# zigduino-v6b.net
KiCad netlist of a schematic drawn in EAGLE
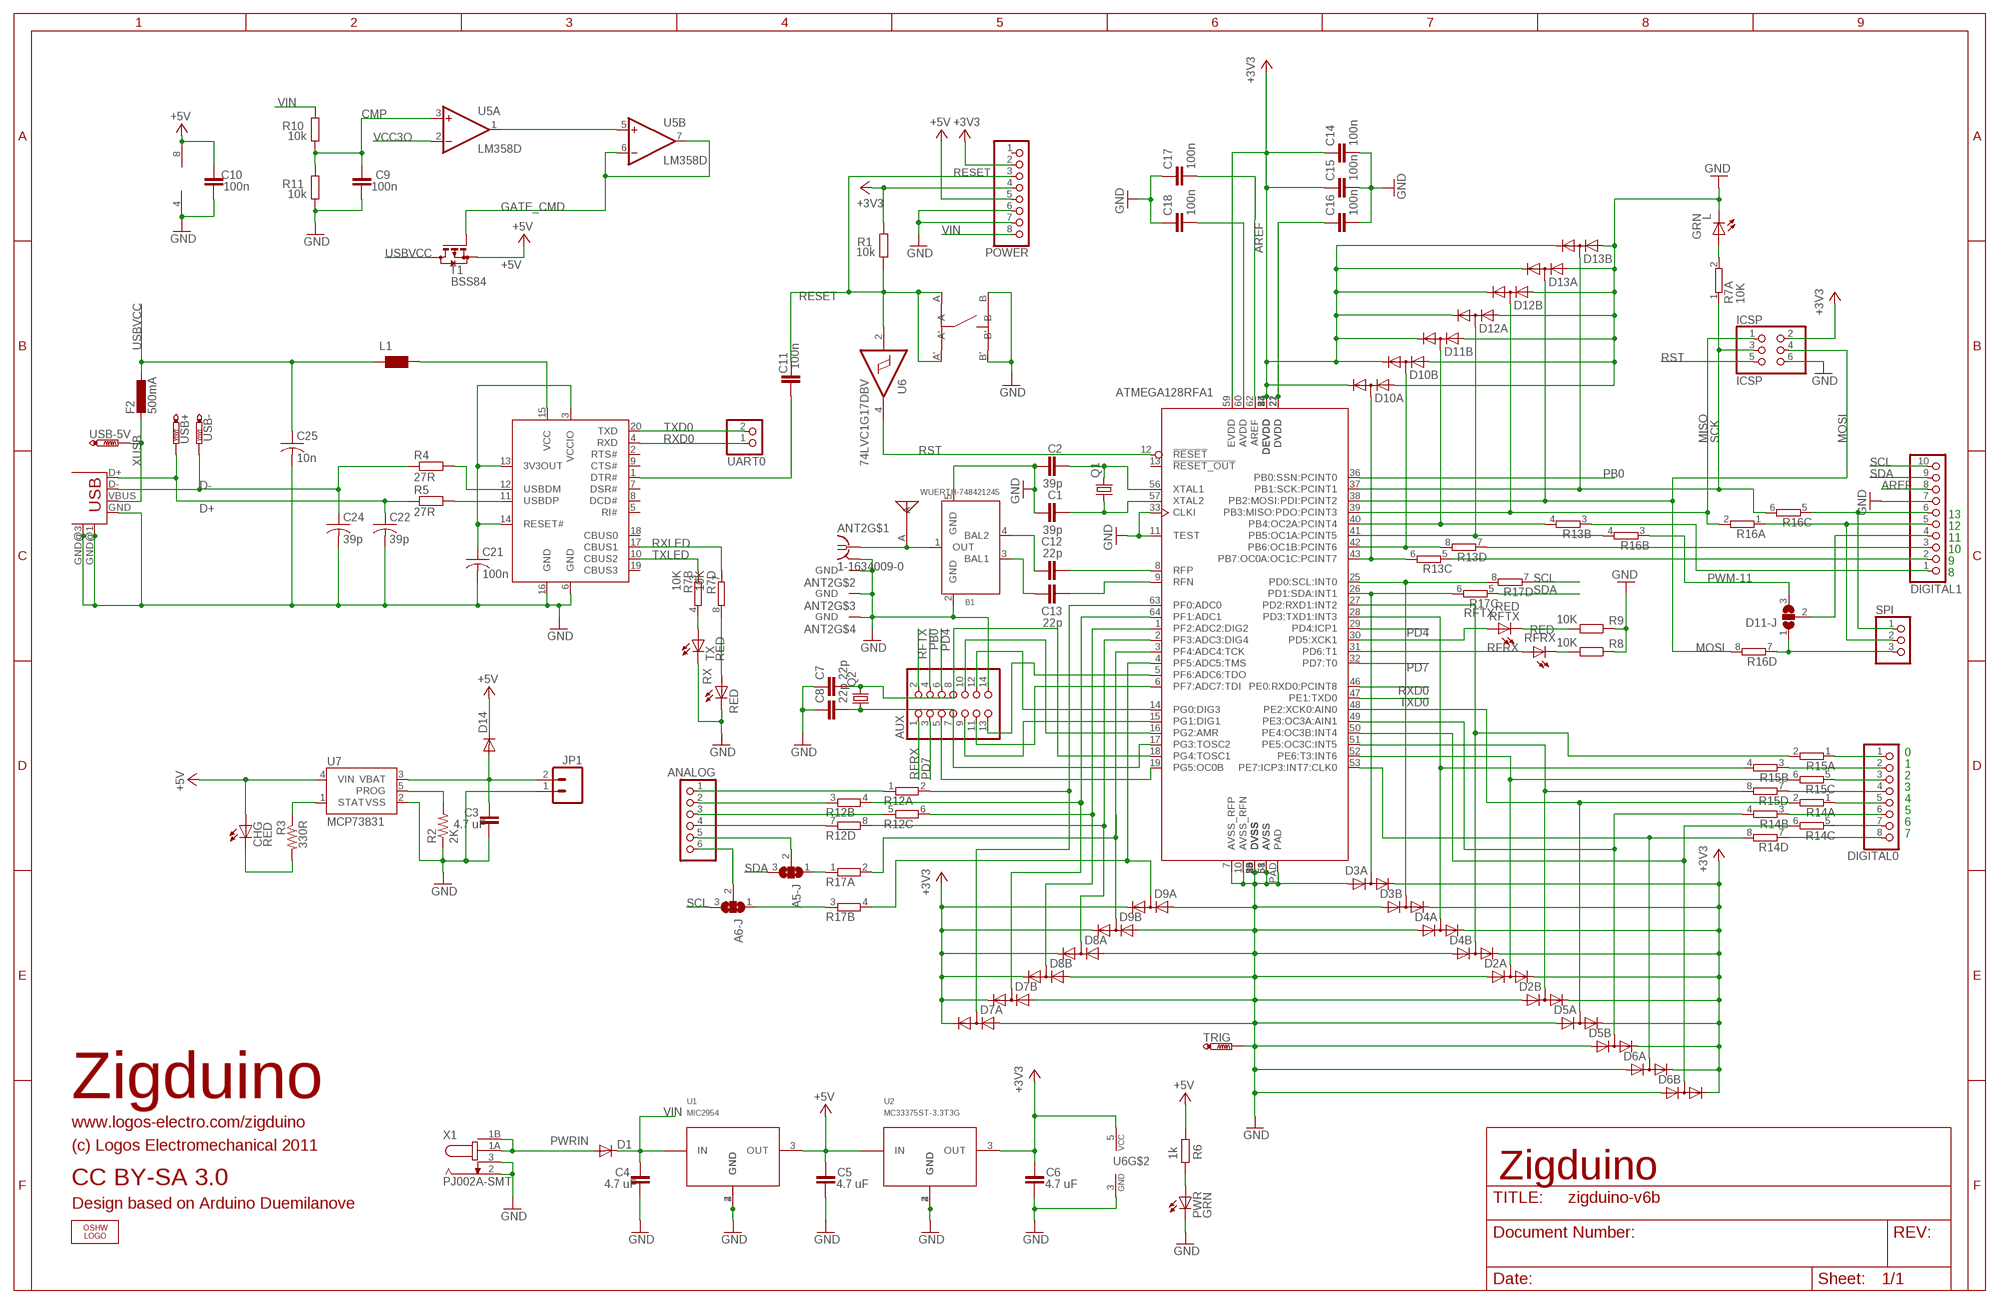
[diagram p0: schematic, sheet 1]

(export (version "E")
  (design (tool "Eeschema 10.0.6"))
  (components
    (comp (ref "A5-J")
      (value "SJ2W")
      (footprint "eagle-import:SJ_2")
      (fields (field (name "PARTNO") "SJ3"))
      (libsource (lib "eagle-import") (part "SJ2W"))
    )
    (comp (ref "A6-J")
      (value "SJ2W")
      (footprint "eagle-import:SJ_2")
      (fields (field (name "PARTNO") "SJ3"))
      (libsource (lib "eagle-import") (part "SJ2W"))
    )
    (comp (ref "ANALOG")
      (value "PINHD-1X6")
      (footprint "eagle-import:1X06")
      (fields (field (name "PARTNO") "19742"))
      (libsource (lib "eagle-import") (part "PINHD-1X6"))
    )
    (comp (ref "ANT1")
      (value "MOLEX-ANT")
      (footprint "eagle-import:MOLEX-ANT")
      (fields (field (name "PARTNO") "0479480001"))
      (libsource (lib "eagle-import") (part "MOLEX-ANT"))
    )
    (comp (ref "ANT2")
      (value "1-1634009-0")
      (footprint "eagle-import:MMCX-THRU")
      (fields (field (name "BOM") "EXCLUDE") (field (name "DNP") "T"))
      (libsource (lib "eagle-import") (part "1-1634009-0"))
    )
    (comp (ref "AUX")
      (value "PINHD-2X7_2.00")
      (footprint "eagle-import:2X07M")
      (fields (field (name "PARTNO") "00217"))
      (libsource (lib "eagle-import") (part "PINHD-2X7_2.00"))
    )
    (comp (ref "B1")
      (value "WUERTH-748421245")
      (footprint "eagle-import:WURTH-BALUN")
      (fields (field (name "PARTNO") "748421245"))
      (libsource (lib "eagle-import") (part "WUERTH-748421245"))
    )
    (comp (ref "C1")
      (value "39p")
      (footprint "eagle-import:C0603")
      (fields (field (name "PARTNO") "C1608C0G1H390J"))
      (libsource (lib "eagle-import") (part "C-EUC0603"))
    )
    (comp (ref "C2")
      (value "39p")
      (footprint "eagle-import:C0603")
      (fields (field (name "PARTNO") "C1608C0G1H390J"))
      (libsource (lib "eagle-import") (part "C-EUC0603"))
    )
    (comp (ref "C3")
      (value "4.7 uF")
      (footprint "eagle-import:C1206")
      (fields (field (name "PARTNO") "C3216Y5V1H475Z"))
      (libsource (lib "eagle-import") (part "C-EUC1206"))
    )
    (comp (ref "C4")
      (value "4.7 uF")
      (footprint "eagle-import:C1206")
      (fields (field (name "PARTNO") "C3216Y5V1H475Z"))
      (libsource (lib "eagle-import") (part "C-EUC1206"))
    )
    (comp (ref "C5")
      (value "4.7 uF")
      (footprint "eagle-import:C1206")
      (fields (field (name "PARTNO") "C3216Y5V1H475Z"))
      (libsource (lib "eagle-import") (part "C-EUC1206"))
    )
    (comp (ref "C6")
      (value "4.7 uF")
      (footprint "eagle-import:C1206")
      (fields (field (name "PARTNO") "C3216Y5V1H475Z"))
      (libsource (lib "eagle-import") (part "C-EUC1206"))
    )
    (comp (ref "C7")
      (value "22p")
      (footprint "eagle-import:C0603")
      (fields (field (name "PARTNO") "GQM1885C1H220JB01D"))
      (libsource (lib "eagle-import") (part "C-EUC0603"))
    )
    (comp (ref "C8")
      (value "22p")
      (footprint "eagle-import:C0603")
      (fields (field (name "PARTNO") "GQM1885C1H220JB01D"))
      (libsource (lib "eagle-import") (part "C-EUC0603"))
    )
    (comp (ref "C9")
      (value "100n")
      (footprint "eagle-import:C0603")
      (fields (field (name "PARTNO") "CC0603MRY5V9BB104"))
      (libsource (lib "eagle-import") (part "C-EUC0603"))
    )
    (comp (ref "C10")
      (value "100n")
      (footprint "eagle-import:C0603")
      (fields (field (name "PARTNO") "CC0603MRY5V9BB104"))
      (libsource (lib "eagle-import") (part "C-EUC0603"))
    )
    (comp (ref "C11")
      (value "100n")
      (footprint "eagle-import:C0603")
      (fields (field (name "PARTNO") "CC0603MRY5V9BB104"))
      (libsource (lib "eagle-import") (part "C-EUC0603"))
    )
    (comp (ref "C12")
      (value "22p")
      (footprint "eagle-import:C0603")
      (fields (field (name "PARTNO") "GQM1885C1H220JB01D"))
      (libsource (lib "eagle-import") (part "C-EUC0603"))
    )
    (comp (ref "C13")
      (value "22p")
      (footprint "eagle-import:C0603")
      (fields (field (name "PARTNO") "GQM1885C1H220JB01D"))
      (libsource (lib "eagle-import") (part "C-EUC0603"))
    )
    (comp (ref "C14")
      (value "100n")
      (footprint "eagle-import:C0603")
      (fields (field (name "PARTNO") "CC0603MRY5V9BB104"))
      (libsource (lib "eagle-import") (part "C-EUC0603"))
    )
    (comp (ref "C15")
      (value "100n")
      (footprint "eagle-import:C0603")
      (fields (field (name "PARTNO") "CC0603MRY5V9BB104"))
      (libsource (lib "eagle-import") (part "C-EUC0603"))
    )
    (comp (ref "C16")
      (value "100n")
      (footprint "eagle-import:C0603")
      (fields (field (name "PARTNO") "CC0603MRY5V9BB104"))
      (libsource (lib "eagle-import") (part "C-EUC0603"))
    )
    (comp (ref "C17")
      (value "100n")
      (footprint "eagle-import:C0603")
      (fields (field (name "PARTNO") "CC0603MRY5V9BB104"))
      (libsource (lib "eagle-import") (part "C-EUC0603"))
    )
    (comp (ref "C18")
      (value "100n")
      (footprint "eagle-import:C0603")
      (fields (field (name "PARTNO") "CC0603MRY5V9BB104"))
      (libsource (lib "eagle-import") (part "C-EUC0603"))
    )
    (comp (ref "C21")
      (value "100n")
      (footprint "eagle-import:C0603")
      (fields (field (name "PARTNO") "CC0603MRY5V9BB104"))
      (libsource (lib "eagle-import") (part "C-USC0603"))
    )
    (comp (ref "C22")
      (value "39p")
      (footprint "eagle-import:C0603")
      (fields (field (name "PARTNO") "C1608C0G1H390J"))
      (libsource (lib "eagle-import") (part "C-USC0603"))
    )
    (comp (ref "C24")
      (value "39p")
      (footprint "eagle-import:C0603")
      (fields (field (name "PARTNO") "C1608C0G1H390J"))
      (libsource (lib "eagle-import") (part "C-USC0603"))
    )
    (comp (ref "C25")
      (value "10n")
      (footprint "eagle-import:C0603")
      (fields (field (name "PARTNO") "GRM188R71H103KA01D"))
      (libsource (lib "eagle-import") (part "C-USC0603"))
    )
    (comp (ref "CHG")
      (value "RED")
      (footprint "eagle-import:CHIP-LED0603")
      (fields (field (name "PARTNO") "LTST-C193KRKT-5A"))
      (libsource (lib "eagle-import") (part "LEDCHIP-LED0603"))
    )
    (comp (ref "D1")
      (value "DIODE-SMB")
      (footprint "eagle-import:SMB")
      (fields (field (name "PARTNO") "B150B-13-F"))
      (libsource (lib "eagle-import") (part "DIODE-SMB"))
    )
    (comp (ref "D2")
      (value "SD103ASDM")
      (footprint "eagle-import:SOT26")
      (fields
        (field (name "BOM") "INCLUDE")
        (field (name "PARTNO") "SD103ASDM-7")
        (field (name "VOLT") "40V")
      )
      (libsource (lib "eagle-import") (part "SD103ASDM"))
    )
    (comp (ref "D3")
      (value "SD103ASDM")
      (footprint "eagle-import:SOT26")
      (fields
        (field (name "BOM") "INCLUDE")
        (field (name "PARTNO") "SD103ASDM-7")
        (field (name "VOLT") "40V")
      )
      (libsource (lib "eagle-import") (part "SD103ASDM"))
    )
    (comp (ref "D4")
      (value "SD103ASDM")
      (footprint "eagle-import:SOT26")
      (fields
        (field (name "PARTNO") "SD103ASDM-7")
        (field (name "VOLT") "40V")
        (field (name "BOM") "INCLUDE")
      )
      (libsource (lib "eagle-import") (part "SD103ASDM"))
    )
    (comp (ref "D5")
      (value "SD103ASDM")
      (footprint "eagle-import:SOT26")
      (fields
        (field (name "PARTNO") "SD103ASDM-7")
        (field (name "VOLT") "40V")
        (field (name "BOM") "INCLUDE")
      )
      (libsource (lib "eagle-import") (part "SD103ASDM"))
    )
    (comp (ref "D6")
      (value "SD103ASDM")
      (footprint "eagle-import:SOT26")
      (fields
        (field (name "PARTNO") "SD103ASDM-7")
        (field (name "VOLT") "40V")
        (field (name "BOM") "INCLUDE")
      )
      (libsource (lib "eagle-import") (part "SD103ASDM"))
    )
    (comp (ref "D7")
      (value "SD103ASDM")
      (footprint "eagle-import:SOT26")
      (fields
        (field (name "BOM") "INCLUDE")
        (field (name "PARTNO") "SD103ASDM-7")
        (field (name "VOLT") "40V")
      )
      (libsource (lib "eagle-import") (part "SD103ASDM"))
    )
    (comp (ref "D8")
      (value "SD103ASDM")
      (footprint "eagle-import:SOT26")
      (fields
        (field (name "BOM") "INCLUDE")
        (field (name "PARTNO") "SD103ASDM-7")
        (field (name "VOLT") "40V")
      )
      (libsource (lib "eagle-import") (part "SD103ASDM"))
    )
    (comp (ref "D9")
      (value "SD103ASDM")
      (footprint "eagle-import:SOT26")
      (fields
        (field (name "PARTNO") "SD103ASDM-7")
        (field (name "BOM") "INCLUDE")
        (field (name "VOLT") "40V")
      )
      (libsource (lib "eagle-import") (part "SD103ASDM"))
    )
    (comp (ref "D10")
      (value "SD103ASDM")
      (footprint "eagle-import:SOT26")
      (fields
        (field (name "PARTNO") "SD103ASDM-7")
        (field (name "BOM") "INCLUDE")
        (field (name "VOLT") "40V")
      )
      (libsource (lib "eagle-import") (part "SD103ASDM"))
    )
    (comp (ref "D11")
      (value "SD103ASDM")
      (footprint "eagle-import:SOT26")
      (fields (field (name "PARTNO") "SD103ASDM-7"))
      (libsource (lib "eagle-import") (part "SD103ASDM"))
    )
    (comp (ref "D11-J")
      (value "SJ2W")
      (footprint "eagle-import:SJ_2")
      (fields (field (name "PARTNO") "SJ3"))
      (libsource (lib "eagle-import") (part "SJ2W"))
    )
    (comp (ref "D12")
      (value "SD103ASDM")
      (footprint "eagle-import:SOT26")
      (fields
        (field (name "BOM") "INCLUDE")
        (field (name "PARTNO") "SD103ASDM-7")
        (field (name "VOLT") "40V")
      )
      (libsource (lib "eagle-import") (part "SD103ASDM"))
    )
    (comp (ref "D13")
      (value "SD103ASDM")
      (footprint "eagle-import:SOT26")
      (fields
        (field (name "PARTNO") "SD103ASDM-7")
        (field (name "VOLT") "40V")
        (field (name "BOM") "INCLUDE")
      )
      (libsource (lib "eagle-import") (part "SD103ASDM"))
    )
    (comp (ref "D14")
      (value "DIODE-SMB")
      (footprint "eagle-import:SMB")
      (fields (field (name "PARTNO") "B150B-13-F"))
      (libsource (lib "eagle-import") (part "DIODE-SMB"))
    )
    (comp (ref "DIGITAL0")
      (value "PINHD-1X8")
      (footprint "eagle-import:1X08")
      (fields (field (name "PARTNO") "19743"))
      (libsource (lib "eagle-import") (part "PINHD-1X8"))
    )
    (comp (ref "DIGITAL1")
      (value "PINHD-1X10")
      (footprint "eagle-import:1X10")
      (fields (field (name "PARTNO") "20083"))
      (libsource (lib "eagle-import") (part "PINHD-1X10"))
    )
    (comp (ref "F2")
      (value "500mA")
      (footprint "eagle-import:L1812")
      (fields (field (name "PARTNO") "MF-MSMF050-2"))
      (libsource (lib "eagle-import") (part "L-EUL1812"))
    )
    (comp (ref "ICSP")
      (value "ICSP")
      (footprint "eagle-import:2X03")
      (fields (field (name "PARTNO") "961206-6404-AR"))
      (libsource (lib "eagle-import") (part "PINHD-2X3"))
    )
    (comp (ref "JP1")
      (value "M02-JST-2MM-SMT")
      (footprint "eagle-import:S2B-PH")
      (fields (field (name "PARTNO") "S2B-PH-SM4-TB(LF)(SN)"))
      (libsource (lib "eagle-import") (part "M02-JST-2MM-SMT"))
    )
    (comp (ref "L")
      (value "GRN")
      (footprint "eagle-import:CHIP-LED0603")
      (fields (field (name "PARTNO") "LTST-C193KGKT-5A"))
      (libsource (lib "eagle-import") (part "LEDCHIP-LED0603"))
    )
    (comp (ref "L1")
      (value "WE-CBF_0805")
      (footprint "eagle-import:0805")
      (fields (field (name "PARTNO") "MI0805K400R-10"))
      (libsource (lib "eagle-import") (part "WE-CBF_0805"))
    )
    (comp (ref "LOGO1")
      (value "OSHW_LOGO_FILLX0200-NT")
      (footprint "eagle-import:OSHW_FILLX200_NOTEXT")
      (libsource (lib "eagle-import") (part "OSHW_LOGO_FILLX0200-NT"))
    )
    (comp (ref "POWER")
      (value "PINHD-1X8")
      (footprint "eagle-import:1X08")
      (fields (field (name "PARTNO") "19743"))
      (libsource (lib "eagle-import") (part "PINHD-1X8"))
    )
    (comp (ref "PWR")
      (value "GRN")
      (footprint "eagle-import:CHIP-LED0603")
      (fields (field (name "PARTNO") "LTST-C193KGKT-5A"))
      (libsource (lib "eagle-import") (part "LEDCHIP-LED0603"))
    )
    (comp (ref "Q1")
      (value "CRYSTALCSM-3X")
      (footprint "eagle-import:CSM-3X")
      (fields (field (name "PARTNO") "ECS-160-20-3X-TR"))
      (libsource (lib "eagle-import") (part "CRYSTALCSM-3X"))
    )
    (comp (ref "Q2")
      (value "CRYSTALTC26H")
      (footprint "eagle-import:TC26H")
      (libsource (lib "eagle-import") (part "CRYSTALTC26H"))
    )
    (comp (ref "R1")
      (value "10k")
      (footprint "eagle-import:R0603")
      (fields (field (name "PARTNO") "RMCF0603FT10K0"))
      (libsource (lib "eagle-import") (part "R-EU_R0603"))
    )
    (comp (ref "R2")
      (value "2K")
      (footprint "eagle-import:R0603")
      (fields (field (name "PARTNO") "RC0603FR-072KL"))
      (libsource (lib "eagle-import") (part "R-US_R0603"))
    )
    (comp (ref "R3")
      (value "330R")
      (footprint "eagle-import:R0603")
      (fields (field (name "PARTNO") "RC0603FR-07330RL"))
      (libsource (lib "eagle-import") (part "R-US_R0603"))
    )
    (comp (ref "R4")
      (value "27R")
      (footprint "eagle-import:R0603")
      (fields (field (name "PARTNO") "RC0603JR-0727RL"))
      (libsource (lib "eagle-import") (part "R-EU_R0603"))
    )
    (comp (ref "R5")
      (value "27R")
      (footprint "eagle-import:R0603")
      (fields (field (name "PARTNO") "RC0603JR-0727RL"))
      (libsource (lib "eagle-import") (part "R-EU_R0603"))
    )
    (comp (ref "R6")
      (value "1k")
      (footprint "eagle-import:R0603")
      (fields (field (name "PARTNO") "RMCF0603FT1K00"))
      (libsource (lib "eagle-import") (part "R-EU_R0603"))
    )
    (comp (ref "R7")
      (value "10K")
      (footprint "eagle-import:CTS742C083-RES")
      (fields (field (name "BOM") "INCLUDE") (field (name "PARTNO") "742C083101JPTR"))
      (libsource (lib "eagle-import") (part "4R-NCTS742C083"))
    )
    (comp (ref "R8")
      (value "10K")
      (footprint "eagle-import:R0603")
      (fields (field (name "PARTNO") "RMCF0603FT1K00"))
      (libsource (lib "eagle-import") (part "R-EU_R0603"))
    )
    (comp (ref "R9")
      (value "10K")
      (footprint "eagle-import:R0603")
      (fields (field (name "PARTNO") "RMCF0603FT1K00"))
      (libsource (lib "eagle-import") (part "R-EU_R0603"))
    )
    (comp (ref "R10")
      (value "10k")
      (footprint "eagle-import:R0603")
      (fields (field (name "PARTNO") "RMCF0603FT10K0"))
      (libsource (lib "eagle-import") (part "R-EU_R0603"))
    )
    (comp (ref "R11")
      (value "10k")
      (footprint "eagle-import:R0603")
      (fields (field (name "PARTNO") "RMCF0603FT10K0"))
      (libsource (lib "eagle-import") (part "R-EU_R0603"))
    )
    (comp (ref "R12")
      (value "4R-NCTS742C083")
      (footprint "eagle-import:CTS742C083-RES")
      (fields (field (name "PARTNO") "742C083101JPTR") (field (name "BOM") "INCLUDE"))
      (libsource (lib "eagle-import") (part "4R-NCTS742C083"))
    )
    (comp (ref "R13")
      (value "4R-NCTS742C083")
      (footprint "eagle-import:CTS742C083-RES")
      (fields (field (name "PARTNO") "742C083101JPTR") (field (name "BOM") "INCLUDE"))
      (libsource (lib "eagle-import") (part "4R-NCTS742C083"))
    )
    (comp (ref "R14")
      (value "4R-NCTS742C083")
      (footprint "eagle-import:CTS742C083-RES")
      (fields (field (name "BOM") "INCLUDE") (field (name "PARTNO") "742C083101JPTR"))
      (libsource (lib "eagle-import") (part "4R-NCTS742C083"))
    )
    (comp (ref "R15")
      (value "4R-NCTS742C083")
      (footprint "eagle-import:CTS742C083-RES")
      (fields (field (name "BOM") "INCLUDE") (field (name "PARTNO") "742C083101JPTR"))
      (libsource (lib "eagle-import") (part "4R-NCTS742C083"))
    )
    (comp (ref "R16")
      (value "4R-NCTS742C083")
      (footprint "eagle-import:CTS742C083-RES")
      (fields (field (name "BOM") "INCLUDE") (field (name "PARTNO") "742C083101JPTR"))
      (libsource (lib "eagle-import") (part "4R-NCTS742C083"))
    )
    (comp (ref "R17")
      (value "4R-NCTS742C083")
      (footprint "eagle-import:CTS742C083-RES")
      (fields (field (name "BOM") "INCLUDE") (field (name "PARTNO") "742C083101JPTR"))
      (libsource (lib "eagle-import") (part "4R-NCTS742C083"))
    )
    (comp (ref "RFRX")
      (value "RED")
      (footprint "eagle-import:CHIP-LED0603")
      (fields (field (name "PARTNO") "LTST-C193KRKT-5A"))
      (libsource (lib "eagle-import") (part "LEDCHIP-LED0603"))
    )
    (comp (ref "RFTX")
      (value "RED")
      (footprint "eagle-import:CHIP-LED0603")
      (fields (field (name "PARTNO") "LTST-C193KRKT-5A"))
      (libsource (lib "eagle-import") (part "LEDCHIP-LED0603"))
    )
    (comp (ref "RX")
      (value "RED")
      (footprint "eagle-import:CHIP-LED0603")
      (fields (field (name "PARTNO") "LTST-C193KRKT-5A"))
      (libsource (lib "eagle-import") (part "LEDCHIP-LED0603"))
    )
    (comp (ref "SPI")
      (value "PINHD-1X3")
      (footprint "eagle-import:1X03")
      (fields (field (name "PARTNO") "20152"))
      (libsource (lib "eagle-import") (part "PINHD-1X3"))
    )
    (comp (ref "SW1")
      (value "EVQ-PSD02K")
      (footprint "eagle-import:EVQPSD02K")
      (libsource (lib "eagle-import") (part "EVQ-PSD02K"))
    )
    (comp (ref "T1")
      (value "BSS84")
      (footprint "eagle-import:SOT23")
      (libsource (lib "eagle-import") (part "BSS84"))
    )
    (comp (ref "TRIG")
      (value "PTR1TP13SQ")
      (footprint "eagle-import:TP13SQ")
      (fields (field (name "PARTNO") "TP13"))
      (libsource (lib "eagle-import") (part "PTR1TP13SQ"))
    )
    (comp (ref "TX")
      (value "RED")
      (footprint "eagle-import:CHIP-LED0603")
      (fields (field (name "PARTNO") "LTST-C193KRKT-5A"))
      (libsource (lib "eagle-import") (part "LEDCHIP-LED0603"))
    )
    (comp (ref "U1")
      (value "MIC2954")
      (footprint "eagle-import:SOT223")
      (fields (field (name "PARTNO") "MIC2954-03WS-TR"))
      (libsource (lib "eagle-import") (part "MIC2954"))
    )
    (comp (ref "U2")
      (value "MC33375ST-3.3T3G")
      (footprint "eagle-import:SOT223")
      (libsource (lib "eagle-import") (part "MIC5201-3.3BS"))
    )
    (comp (ref "U3")
      (value "ATMEGA128RFA1")
      (footprint "eagle-import:QFN64")
      (fields (field (name "PARTNO") "ATMEGA128RFA1-ZUR"))
      (libsource (lib "eagle-import") (part "ATMEGA128RFA1"))
    )
    (comp (ref "U4")
      (value "FT231XS-R")
      (footprint "eagle-import:SSOP20")
      (libsource (lib "eagle-import") (part "FT231XS-R"))
    )
    (comp (ref "U5")
      (value "LM358D")
      (footprint "eagle-import:SO08")
      (fields (field (name "PARTNO") "LM358DR"))
      (libsource (lib "eagle-import") (part "LM358D"))
    )
    (comp (ref "U6")
      (value "74LVC1G17DBV")
      (footprint "eagle-import:SOT23-5")
      (fields (field (name "BOM") "INCLUDE") (field (name "PARTNO") "SN74LVC1G17DBVR"))
      (libsource (lib "eagle-import") (part "741G17DBVLVC"))
    )
    (comp (ref "U7")
      (value "MCP73831")
      (footprint "eagle-import:SOT23-5")
      (fields (field (name "PARTNO") "MCP73831T-2ACI/OT"))
      (libsource (lib "eagle-import") (part "MCP73831"))
    )
    (comp (ref "UART0")
      (value "PINHD-1X2")
      (footprint "eagle-import:1X02")
      (fields (field (name "PARTNO") "00522"))
      (libsource (lib "eagle-import") (part "PINHD-1X2"))
    )
    (comp (ref "USB")
      (value "USB-MB-S")
      (footprint "eagle-import:USB-MB-S")
      (fields (field (name "PARTNO") "20236"))
      (libsource (lib "eagle-import") (part "USB-MB-S"))
    )
    (comp (ref "USB+")
      (value "PTR1TP13SQ")
      (footprint "eagle-import:TP13SQ")
      (fields (field (name "PARTNO") "TP13"))
      (libsource (lib "eagle-import") (part "PTR1TP13SQ"))
    )
    (comp (ref "USB-")
      (value "PTR1TP13SQ")
      (footprint "eagle-import:TP13SQ")
      (fields (field (name "PARTNO") "TP13"))
      (libsource (lib "eagle-import") (part "PTR1TP13SQ"))
    )
    (comp (ref "USB-5V")
      (value "PTR1TP13SQ")
      (footprint "eagle-import:TP13SQ")
      (fields (field (name "PARTNO") "TP13"))
      (libsource (lib "eagle-import") (part "PTR1TP13SQ"))
    )
    (comp (ref "X1")
      (value "PJ002A-SMT")
      (footprint "eagle-import:PJ002A-SMT")
      (fields (field (name "PARTNO") "PJ-002AH-SMT"))
      (libsource (lib "eagle-import") (part "PJ002A-SMT"))
    )
  )
  (nets
    (net (code "1") (name "+3V3") (class "Default")
      (node (ref "C14") (pin "1") (pinfunction "1_1") (pintype "passive"))
      (node (ref "C15") (pin "1") (pinfunction "1_1") (pintype "passive"))
      (node (ref "C6") (pin "1") (pinfunction "1_1") (pintype "passive"))
      (node (ref "D10") (pin "2") (pinfunction "C_2") (pintype "passive"))
      (node (ref "D10") (pin "5") (pinfunction "C_5") (pintype "passive"))
      (node (ref "D11") (pin "5") (pinfunction "C_5") (pintype "passive"))
      (node (ref "D12") (pin "2") (pinfunction "C_2") (pintype "passive"))
      (node (ref "D12") (pin "5") (pinfunction "C_5") (pintype "passive"))
      (node (ref "D13") (pin "2") (pinfunction "C_2") (pintype "passive"))
      (node (ref "D13") (pin "5") (pinfunction "C_5") (pintype "passive"))
      (node (ref "D2") (pin "2") (pinfunction "C_2") (pintype "passive"))
      (node (ref "D2") (pin "5") (pinfunction "C_5") (pintype "passive"))
      (node (ref "D3") (pin "2") (pinfunction "C_2") (pintype "passive"))
      (node (ref "D3") (pin "5") (pinfunction "C_5") (pintype "passive"))
      (node (ref "D4") (pin "2") (pinfunction "C_2") (pintype "passive"))
      (node (ref "D4") (pin "5") (pinfunction "C_5") (pintype "passive"))
      (node (ref "D5") (pin "2") (pinfunction "C_2") (pintype "passive"))
      (node (ref "D5") (pin "5") (pinfunction "C_5") (pintype "passive"))
      (node (ref "D6") (pin "2") (pinfunction "C_2") (pintype "passive"))
      (node (ref "D6") (pin "5") (pinfunction "C_5") (pintype "passive"))
      (node (ref "D7") (pin "2") (pinfunction "C_2") (pintype "passive"))
      (node (ref "D7") (pin "5") (pinfunction "C_5") (pintype "passive"))
      (node (ref "D8") (pin "2") (pinfunction "C_2") (pintype "passive"))
      (node (ref "D8") (pin "5") (pinfunction "C_5") (pintype "passive"))
      (node (ref "D9") (pin "2") (pinfunction "C_2") (pintype "passive"))
      (node (ref "D9") (pin "5") (pinfunction "C_5") (pintype "passive"))
      (node (ref "ICSP") (pin "2") (pinfunction "2_2") (pintype "passive"))
      (node (ref "POWER") (pin "2") (pinfunction "2_2") (pintype "passive"))
      (node (ref "POWER") (pin "4") (pinfunction "4_4") (pintype "passive"))
      (node (ref "R1") (pin "2") (pinfunction "2_2") (pintype "passive"))
      (node (ref "U2") (pin "3") (pinfunction "OUT_3") (pintype "bidirectional"))
      (node (ref "U3") (pin "23") (pinfunction "DEVDD_23") (pintype "bidirectional"))
      (node (ref "U3") (pin "34") (pinfunction "DEVDD_34") (pintype "bidirectional"))
      (node (ref "U3") (pin "44") (pinfunction "DEVDD_44") (pintype "bidirectional"))
      (node (ref "U3") (pin "54") (pinfunction "DEVDD_54") (pintype "bidirectional"))
      (node (ref "U3") (pin "59") (pinfunction "EVDD_59") (pintype "bidirectional"))
      (node (ref "U6") (pin "5") (pinfunction "VCC_5") (pintype "power_in"))
    )
    (net (code "2") (name "+5V") (class "Default")
      (node (ref "C10") (pin "2") (pinfunction "2_2") (pintype "passive"))
      (node (ref "C5") (pin "1") (pinfunction "1_1") (pintype "passive"))
      (node (ref "CHG") (pin "A") (pinfunction "A_A") (pintype "passive"))
      (node (ref "D14") (pin "C") (pinfunction "C_C") (pintype "passive"))
      (node (ref "POWER") (pin "5") (pinfunction "5_5") (pintype "passive"))
      (node (ref "R6") (pin "1") (pinfunction "1_1") (pintype "passive"))
      (node (ref "T1") (pin "2") (pinfunction "S_2") (pintype "passive"))
      (node (ref "U1") (pin "3") (pinfunction "OUT_3") (pintype "bidirectional"))
      (node (ref "U2") (pin "1") (pinfunction "IN_1") (pintype "bidirectional"))
      (node (ref "U5") (pin "8") (pinfunction "V+_8") (pintype "power_in"))
      (node (ref "U7") (pin "4") (pinfunction "VIN_4") (pintype "power_in"))
    )
    (net (code "3") (name "/AREF") (class "Default")
      (node (ref "C17") (pin "2") (pinfunction "2_2") (pintype "passive"))
      (node (ref "DIGITAL1") (pin "8") (pinfunction "8_8") (pintype "passive"))
      (node (ref "U3") (pin "62") (pinfunction "AREF_62") (pintype "bidirectional"))
    )
    (net (code "4") (name "/CMP") (class "Default")
      (node (ref "C9") (pin "2") (pinfunction "2_2") (pintype "passive"))
      (node (ref "R10") (pin "1") (pinfunction "1_1") (pintype "passive"))
      (node (ref "R11") (pin "2") (pinfunction "2_2") (pintype "passive"))
      (node (ref "U5") (pin "3") (pinfunction "+IN_3") (pintype "input"))
    )
    (net (code "5") (name "/D+") (class "Default")
      (node (ref "C22") (pin "1") (pinfunction "1_1") (pintype "passive"))
      (node (ref "R5") (pin "1") (pinfunction "1_1") (pintype "passive"))
      (node (ref "USB") (pin "D+") (pinfunction "D+_D+") (pintype "bidirectional"))
      (node (ref "USB+") (pin "TP") (pinfunction "TP_TP") (pintype "input"))
    )
    (net (code "6") (name "/D-") (class "Default")
      (node (ref "C24") (pin "1") (pinfunction "1_1") (pintype "passive"))
      (node (ref "R4") (pin "1") (pinfunction "1_1") (pintype "passive"))
      (node (ref "USB") (pin "D-") (pinfunction "D-_D-") (pintype "bidirectional"))
      (node (ref "USB-") (pin "TP") (pinfunction "TP_TP") (pintype "input"))
    )
    (net (code "7") (name "/GATE_CMD") (class "Default")
      (node (ref "T1") (pin "1") (pinfunction "G_1") (pintype "passive"))
      (node (ref "U5") (pin "6") (pinfunction "-IN_6") (pintype "input"))
      (node (ref "U5") (pin "7") (pinfunction "OUT_7") (pintype "output"))
    )
    (net (code "8") (name "/MISO") (class "Default")
      (node (ref "D12") (pin "1") (pinfunction "AC_1") (pintype "passive"))
      (node (ref "ICSP") (pin "1") (pinfunction "1_1") (pintype "passive"))
      (node (ref "R16") (pin "2") (pinfunction "2_2") (pintype "passive"))
      (node (ref "U3") (pin "39") (pinfunction "PB3:MISO:PDO:PCINT3_39") (pintype "bidirectional"))
    )
    (net (code "9") (name "/MOSI") (class "Default")
      (node (ref "D13") (pin "4") (pinfunction "AC_4") (pintype "passive"))
      (node (ref "ICSP") (pin "4") (pinfunction "4_4") (pintype "passive"))
      (node (ref "R16") (pin "8") (pinfunction "2_8") (pintype "passive"))
      (node (ref "U3") (pin "38") (pinfunction "PB2:MOSI:PDI:PCINT2_38") (pintype "bidirectional"))
    )
    (net (code "10") (name "/PB0") (class "Default")
      (node (ref "AUX") (pin "4") (pinfunction "4_4") (pintype "passive"))
      (node (ref "U3") (pin "36") (pinfunction "PB0:SSN:PCINT0_36") (pintype "bidirectional"))
    )
    (net (code "11") (name "/PD4") (class "Default")
      (node (ref "AUX") (pin "6") (pinfunction "6_6") (pintype "passive"))
      (node (ref "U3") (pin "29") (pinfunction "PD4:ICP1_29") (pintype "bidirectional"))
    )
    (net (code "12") (name "/PD7") (class "Default")
      (node (ref "AUX") (pin "3") (pinfunction "3_3") (pintype "passive"))
      (node (ref "U3") (pin "32") (pinfunction "PD7:T0_32") (pintype "bidirectional"))
    )
    (net (code "13") (name "/PWM-11") (class "Default")
      (node (ref "D11-J") (pin "3") (pinfunction "3_3") (pintype "passive"))
      (node (ref "R16") (pin "3") (pinfunction "1_3") (pintype "passive"))
    )
    (net (code "14") (name "/PWRIN") (class "Default")
      (node (ref "D1") (pin "A") (pinfunction "A_A") (pintype "passive"))
      (node (ref "X1") (pin "1A") (pinfunction "1A_1A") (pintype "passive"))
      (node (ref "X1") (pin "1B") (pinfunction "1B_1B") (pintype "passive"))
    )
    (net (code "15") (name "/RESET") (class "Default")
      (node (ref "C11") (pin "2") (pinfunction "2_2") (pintype "passive"))
      (node (ref "POWER") (pin "3") (pinfunction "3_3") (pintype "passive"))
      (node (ref "R1") (pin "1") (pinfunction "1_1") (pintype "passive"))
      (node (ref "SW1") (pin "A") (pinfunction "A_A") (pintype "bidirectional"))
      (node (ref "SW1") (pin "A'") (pinfunction "A'_A'") (pintype "bidirectional"))
      (node (ref "U6") (pin "2") (pinfunction "I_2") (pintype "input"))
    )
    (net (code "16") (name "/RFRX") (class "Default")
      (node (ref "AUX") (pin "1") (pinfunction "1_1") (pintype "passive"))
      (node (ref "RFRX") (pin "A") (pinfunction "A_A") (pintype "passive"))
      (node (ref "U3") (pin "31") (pinfunction "PD6:T1_31") (pintype "bidirectional"))
    )
    (net (code "17") (name "/RFTX") (class "Default")
      (node (ref "AUX") (pin "2") (pinfunction "2_2") (pintype "passive"))
      (node (ref "RFTX") (pin "A") (pinfunction "A_A") (pintype "passive"))
      (node (ref "U3") (pin "30") (pinfunction "PD5:XCK1_30") (pintype "bidirectional"))
    )
    (net (code "18") (name "/RST") (class "Default")
      (node (ref "ICSP") (pin "5") (pinfunction "5_5") (pintype "passive"))
      (node (ref "U3") (pin "12") (pinfunction "~{RESET}_12") (pintype "bidirectional"))
      (node (ref "U6") (pin "4") (pinfunction "O_4") (pintype "output"))
    )
    (net (code "19") (name "/RXD0") (class "Default")
      (node (ref "U3") (pin "46") (pinfunction "PE0:RXD0:PCINT8_46") (pintype "bidirectional"))
      (node (ref "U4") (pin "4") (pinfunction "RXD_4") (pintype "bidirectional"))
      (node (ref "UART0") (pin "1") (pinfunction "1_1") (pintype "passive"))
    )
    (net (code "20") (name "/RXLED") (class "Default")
      (node (ref "R7") (pin "7") (pinfunction "1_7") (pintype "passive"))
      (node (ref "U4") (pin "17") (pinfunction "CBUS1_17") (pintype "bidirectional"))
    )
    (net (code "21") (name "/SCK") (class "Default")
      (node (ref "D13") (pin "1") (pinfunction "AC_1") (pintype "passive"))
      (node (ref "ICSP") (pin "3") (pinfunction "3_3") (pintype "passive"))
      (node (ref "R16") (pin "6") (pinfunction "2_6") (pintype "passive"))
      (node (ref "R7") (pin "1") (pinfunction "1_1") (pintype "passive"))
      (node (ref "U3") (pin "37") (pinfunction "PB1:SCK:PCINT1_37") (pintype "bidirectional"))
    )
    (net (code "22") (name "/SCL") (class "Default")
      (node (ref "A6-J") (pin "3") (pinfunction "3_3") (pintype "passive"))
      (node (ref "DIGITAL1") (pin "10") (pinfunction "10_10") (pintype "passive"))
      (node (ref "R17") (pin "7") (pinfunction "1_7") (pintype "passive"))
    )
    (net (code "23") (name "/SDA") (class "Default")
      (node (ref "A5-J") (pin "3") (pinfunction "3_3") (pintype "passive"))
      (node (ref "DIGITAL1") (pin "9") (pinfunction "9_9") (pintype "passive"))
      (node (ref "R17") (pin "5") (pinfunction "1_5") (pintype "passive"))
    )
    (net (code "24") (name "/TXD0") (class "Default")
      (node (ref "U3") (pin "47") (pinfunction "PE1:TXD0_47") (pintype "bidirectional"))
      (node (ref "U4") (pin "20") (pinfunction "TXD_20") (pintype "bidirectional"))
      (node (ref "UART0") (pin "2") (pinfunction "2_2") (pintype "passive"))
    )
    (net (code "25") (name "/TXLED") (class "Default")
      (node (ref "R7") (pin "3") (pinfunction "1_3") (pintype "passive"))
      (node (ref "U4") (pin "10") (pinfunction "CBUS2_10") (pintype "bidirectional"))
    )
    (net (code "26") (name "/USBVCC") (class "Default")
      (node (ref "C25") (pin "1") (pinfunction "1_1") (pintype "passive"))
      (node (ref "F2") (pin "1") (pinfunction "1_1") (pintype "passive"))
      (node (ref "L1") (pin "1") (pinfunction "1_1") (pintype "passive"))
      (node (ref "T1") (pin "3") (pinfunction "D_3") (pintype "passive"))
    )
    (net (code "27") (name "/VCC3O") (class "Default")
      (node (ref "U5") (pin "2") (pinfunction "-IN_2") (pintype "input"))
    )
    (net (code "28") (name "/VIN") (class "Default")
      (node (ref "C4") (pin "1") (pinfunction "1_1") (pintype "passive"))
      (node (ref "D1") (pin "C") (pinfunction "C_C") (pintype "passive"))
      (node (ref "POWER") (pin "8") (pinfunction "8_8") (pintype "passive"))
      (node (ref "R10") (pin "2") (pinfunction "2_2") (pintype "passive"))
      (node (ref "U1") (pin "1") (pinfunction "IN_1") (pintype "bidirectional"))
    )
    (net (code "29") (name "/XUSB") (class "Default")
      (node (ref "F2") (pin "2") (pinfunction "2_2") (pintype "passive"))
      (node (ref "USB") (pin "VBUS") (pinfunction "VBUS_VBUS") (pintype "bidirectional"))
      (node (ref "USB-5V") (pin "TP") (pinfunction "TP_TP") (pintype "input"))
    )
    (net (code "30") (name "GND") (class "Default")
      (node (ref "ANT2") (pin "G@0") (pinfunction "GND_G@0") (pintype "power_in"))
      (node (ref "ANT2") (pin "G@1") (pinfunction "GND_G@1") (pintype "power_in"))
      (node (ref "ANT2") (pin "G@2") (pinfunction "GND_G@2") (pintype "power_in"))
      (node (ref "ANT2") (pin "G@3") (pinfunction "GND_G@3") (pintype "power_in"))
      (node (ref "AUX") (pin "14") (pinfunction "14_14") (pintype "passive"))
      (node (ref "B1") (pin "2") (pinfunction "GND_2") (pintype "bidirectional"))
      (node (ref "B1") (pin "5") (pinfunction "GND_5") (pintype "bidirectional"))
      (node (ref "C1") (pin "1") (pinfunction "1_1") (pintype "passive"))
      (node (ref "C10") (pin "1") (pinfunction "1_1") (pintype "passive"))
      (node (ref "C14") (pin "2") (pinfunction "2_2") (pintype "passive"))
      (node (ref "C15") (pin "2") (pinfunction "2_2") (pintype "passive"))
      (node (ref "C16") (pin "2") (pinfunction "2_2") (pintype "passive"))
      (node (ref "C17") (pin "1") (pinfunction "1_1") (pintype "passive"))
      (node (ref "C18") (pin "1") (pinfunction "1_1") (pintype "passive"))
      (node (ref "C2") (pin "1") (pinfunction "1_1") (pintype "passive"))
      (node (ref "C21") (pin "2") (pinfunction "2_2") (pintype "passive"))
      (node (ref "C22") (pin "2") (pinfunction "2_2") (pintype "passive"))
      (node (ref "C24") (pin "2") (pinfunction "2_2") (pintype "passive"))
      (node (ref "C25") (pin "2") (pinfunction "2_2") (pintype "passive"))
      (node (ref "C3") (pin "2") (pinfunction "2_2") (pintype "passive"))
      (node (ref "C4") (pin "2") (pinfunction "2_2") (pintype "passive"))
      (node (ref "C5") (pin "2") (pinfunction "2_2") (pintype "passive"))
      (node (ref "C6") (pin "2") (pinfunction "2_2") (pintype "passive"))
      (node (ref "C7") (pin "1") (pinfunction "1_1") (pintype "passive"))
      (node (ref "C8") (pin "1") (pinfunction "1_1") (pintype "passive"))
      (node (ref "C9") (pin "1") (pinfunction "1_1") (pintype "passive"))
      (node (ref "D10") (pin "3") (pinfunction "A_3") (pintype "passive"))
      (node (ref "D10") (pin "6") (pinfunction "A_6") (pintype "passive"))
      (node (ref "D11") (pin "6") (pinfunction "A_6") (pintype "passive"))
      (node (ref "D12") (pin "3") (pinfunction "A_3") (pintype "passive"))
      (node (ref "D12") (pin "6") (pinfunction "A_6") (pintype "passive"))
      (node (ref "D13") (pin "3") (pinfunction "A_3") (pintype "passive"))
      (node (ref "D13") (pin "6") (pinfunction "A_6") (pintype "passive"))
      (node (ref "D2") (pin "3") (pinfunction "A_3") (pintype "passive"))
      (node (ref "D2") (pin "6") (pinfunction "A_6") (pintype "passive"))
      (node (ref "D3") (pin "3") (pinfunction "A_3") (pintype "passive"))
      (node (ref "D3") (pin "6") (pinfunction "A_6") (pintype "passive"))
      (node (ref "D4") (pin "3") (pinfunction "A_3") (pintype "passive"))
      (node (ref "D4") (pin "6") (pinfunction "A_6") (pintype "passive"))
      (node (ref "D5") (pin "3") (pinfunction "A_3") (pintype "passive"))
      (node (ref "D5") (pin "6") (pinfunction "A_6") (pintype "passive"))
      (node (ref "D6") (pin "3") (pinfunction "A_3") (pintype "passive"))
      (node (ref "D6") (pin "6") (pinfunction "A_6") (pintype "passive"))
      (node (ref "D7") (pin "3") (pinfunction "A_3") (pintype "passive"))
      (node (ref "D7") (pin "6") (pinfunction "A_6") (pintype "passive"))
      (node (ref "D8") (pin "3") (pinfunction "A_3") (pintype "passive"))
      (node (ref "D8") (pin "6") (pinfunction "A_6") (pintype "passive"))
      (node (ref "D9") (pin "3") (pinfunction "A_3") (pintype "passive"))
      (node (ref "D9") (pin "6") (pinfunction "A_6") (pintype "passive"))
      (node (ref "DIGITAL1") (pin "7") (pinfunction "7_7") (pintype "passive"))
      (node (ref "ICSP") (pin "6") (pinfunction "6_6") (pintype "passive"))
      (node (ref "JP1") (pin "1") (pinfunction "1_1") (pintype "passive"))
      (node (ref "L") (pin "C") (pinfunction "C_C") (pintype "passive"))
      (node (ref "POWER") (pin "6") (pinfunction "6_6") (pintype "passive"))
      (node (ref "POWER") (pin "7") (pinfunction "7_7") (pintype "passive"))
      (node (ref "PWR") (pin "C") (pinfunction "C_C") (pintype "passive"))
      (node (ref "R11") (pin "1") (pinfunction "1_1") (pintype "passive"))
      (node (ref "R2") (pin "1") (pinfunction "1_1") (pintype "passive"))
      (node (ref "R8") (pin "1") (pinfunction "1_1") (pintype "passive"))
      (node (ref "R9") (pin "1") (pinfunction "1_1") (pintype "passive"))
      (node (ref "RX") (pin "C") (pinfunction "C_C") (pintype "passive"))
      (node (ref "SW1") (pin "B") (pinfunction "B_B") (pintype "bidirectional"))
      (node (ref "SW1") (pin "B'") (pinfunction "B'_B'") (pintype "bidirectional"))
      (node (ref "TRIG") (pin "TP") (pinfunction "TP_TP") (pintype "input"))
      (node (ref "TX") (pin "C") (pinfunction "C_C") (pintype "passive"))
      (node (ref "U1") (pin "2") (pinfunction "GND_2") (pintype "bidirectional"))
      (node (ref "U1") (pin "4") (pinfunction "GND_4") (pintype "bidirectional"))
      (node (ref "U2") (pin "2") (pinfunction "GND_2") (pintype "bidirectional"))
      (node (ref "U2") (pin "4") (pinfunction "GND_4") (pintype "bidirectional"))
      (node (ref "U3") (pin "10") (pinfunction "AVSS_RFN_10") (pintype "bidirectional"))
      (node (ref "U3") (pin "11") (pinfunction "TEST_11") (pintype "bidirectional"))
      (node (ref "U3") (pin "20") (pinfunction "DVSS_20") (pintype "bidirectional"))
      (node (ref "U3") (pin "24") (pinfunction "DVSS_24") (pintype "bidirectional"))
      (node (ref "U3") (pin "33") (pinfunction "CLKI_33") (pintype "bidirectional"))
      (node (ref "U3") (pin "35") (pinfunction "DVSS_35") (pintype "bidirectional"))
      (node (ref "U3") (pin "45") (pinfunction "DVSS_45") (pintype "bidirectional"))
      (node (ref "U3") (pin "55") (pinfunction "DVSS_55") (pintype "bidirectional"))
      (node (ref "U3") (pin "58") (pinfunction "AVSS_58") (pintype "bidirectional"))
      (node (ref "U3") (pin "61") (pinfunction "AVSS_61") (pintype "bidirectional"))
      (node (ref "U3") (pin "7") (pinfunction "AVSS_RFP_7") (pintype "bidirectional"))
      (node (ref "U3") (pin "PAD") (pinfunction "PAD_PAD") (pintype "bidirectional"))
      (node (ref "U4") (pin "16") (pinfunction "GND_16") (pintype "bidirectional"))
      (node (ref "U4") (pin "6") (pinfunction "GND_6") (pintype "bidirectional"))
      (node (ref "U5") (pin "4") (pinfunction "V-_4") (pintype "power_in"))
      (node (ref "U6") (pin "3") (pinfunction "GND_3") (pintype "power_in"))
      (node (ref "U7") (pin "2") (pinfunction "VSS_2") (pintype "power_in"))
      (node (ref "USB") (pin "GND") (pinfunction "GND_GND") (pintype "bidirectional"))
      (node (ref "USB") (pin "GND@1") (pinfunction "GND_GND@1") (pintype "bidirectional"))
      (node (ref "USB") (pin "GND@3") (pinfunction "GND_GND@3") (pintype "bidirectional"))
      (node (ref "X1") (pin "2") (pinfunction "2_2") (pintype "passive"))
      (node (ref "X1") (pin "3") (pinfunction "3_3") (pintype "passive"))
    )
    (net (code "31") (name "Net-(A5-J-Pad1)") (class "Default")
      (node (ref "A5-J") (pin "1") (pinfunction "1_1") (pintype "passive"))
      (node (ref "R17") (pin "1") (pinfunction "1_1") (pintype "passive"))
    )
    (net (code "32") (name "Net-(A5-J-Pad2)") (class "Default")
      (node (ref "A5-J") (pin "2") (pinfunction "2_2") (pintype "passive"))
      (node (ref "ANALOG") (pin "5") (pinfunction "5_5") (pintype "passive"))
    )
    (net (code "33") (name "Net-(A6-J-Pad2)") (class "Default")
      (node (ref "A6-J") (pin "2") (pinfunction "2_2") (pintype "passive"))
      (node (ref "ANALOG") (pin "6") (pinfunction "6_6") (pintype "passive"))
    )
    (net (code "34") (name "Net-(ANALOG-Pad1)") (class "Default")
      (node (ref "ANALOG") (pin "1") (pinfunction "1_1") (pintype "passive"))
      (node (ref "R12") (pin "1") (pinfunction "1_1") (pintype "passive"))
    )
    (net (code "35") (name "Net-(ANT2A-1)") (class "Default")
      (node (ref "ANT1") (pin "A") (pinfunction "A_A") (pintype "bidirectional"))
      (node (ref "ANT2") (pin "C") (pinfunction "1_C") (pintype "passive"))
      (node (ref "B1") (pin "1") (pinfunction "OUT_1") (pintype "bidirectional"))
    )
    (net (code "36") (name "Net-(B1-BAL1)") (class "Default")
      (node (ref "B1") (pin "3") (pinfunction "BAL1_3") (pintype "bidirectional"))
      (node (ref "C13") (pin "1") (pinfunction "1_1") (pintype "passive"))
    )
    (net (code "37") (name "Net-(B1-BAL2)") (class "Default")
      (node (ref "B1") (pin "4") (pinfunction "BAL2_4") (pintype "bidirectional"))
      (node (ref "C12") (pin "1") (pinfunction "1_1") (pintype "passive"))
    )
    (net (code "38") (name "Net-(C16-Pad1)") (class "Default")
      (node (ref "C16") (pin "1") (pinfunction "1_1") (pintype "passive"))
      (node (ref "U3") (pin "21") (pinfunction "DVDD_21") (pintype "bidirectional"))
      (node (ref "U3") (pin "22") (pinfunction "DVDD_22") (pintype "bidirectional"))
    )
    (net (code "39") (name "Net-(CHG-PadC)") (class "Default")
      (node (ref "CHG") (pin "C") (pinfunction "C_C") (pintype "passive"))
      (node (ref "R3") (pin "2") (pinfunction "2_2") (pintype "passive"))
    )
    (net (code "40") (name "Net-(D2A-AC)") (class "Default")
      (node (ref "D2") (pin "4") (pinfunction "AC_4") (pintype "passive"))
      (node (ref "R15") (pin "6") (pinfunction "2_6") (pintype "passive"))
      (node (ref "U3") (pin "52") (pinfunction "PE6:T3:INT6_52") (pintype "bidirectional"))
    )
    (net (code "41") (name "Net-(D2B-AC)") (class "Default")
      (node (ref "D2") (pin "1") (pinfunction "AC_1") (pintype "passive"))
      (node (ref "R15") (pin "8") (pinfunction "2_8") (pintype "passive"))
      (node (ref "U3") (pin "51") (pinfunction "PE5:OC3C:INT5_51") (pintype "bidirectional"))
    )
    (net (code "42") (name "Net-(D3A-AC)") (class "Default")
      (node (ref "D3") (pin "4") (pinfunction "AC_4") (pintype "passive"))
      (node (ref "R17") (pin "6") (pinfunction "2_6") (pintype "passive"))
      (node (ref "U3") (pin "26") (pinfunction "PD1:SDA:INT1_26") (pintype "bidirectional"))
    )
    (net (code "43") (name "Net-(D3B-AC)") (class "Default")
      (node (ref "D3") (pin "1") (pinfunction "AC_1") (pintype "passive"))
      (node (ref "R17") (pin "8") (pinfunction "2_8") (pintype "passive"))
      (node (ref "U3") (pin "25") (pinfunction "PD0:SCL:INT0_25") (pintype "bidirectional"))
    )
    (net (code "44") (name "Net-(D4A-AC)") (class "Default")
      (node (ref "D4") (pin "4") (pinfunction "AC_4") (pintype "passive"))
      (node (ref "R15") (pin "4") (pinfunction "2_4") (pintype "passive"))
      (node (ref "U3") (pin "28") (pinfunction "PD3:TXD1:INT3_28") (pintype "bidirectional"))
    )
    (net (code "45") (name "Net-(D4B-AC)") (class "Default")
      (node (ref "D4") (pin "1") (pinfunction "AC_1") (pintype "passive"))
      (node (ref "R15") (pin "2") (pinfunction "2_2") (pintype "passive"))
      (node (ref "U3") (pin "27") (pinfunction "PD2:RXD1:INT2_27") (pintype "bidirectional"))
    )
    (net (code "46") (name "Net-(D5A-AC)") (class "Default")
      (node (ref "D5") (pin "4") (pinfunction "AC_4") (pintype "passive"))
      (node (ref "R14") (pin "2") (pinfunction "2_2") (pintype "passive"))
      (node (ref "U3") (pin "48") (pinfunction "PE2:XCK0:AIN0_48") (pintype "bidirectional"))
    )
    (net (code "47") (name "Net-(D5B-AC)") (class "Default")
      (node (ref "D5") (pin "1") (pinfunction "AC_1") (pintype "passive"))
      (node (ref "R14") (pin "4") (pinfunction "2_4") (pintype "passive"))
      (node (ref "U3") (pin "49") (pinfunction "PE3:OC3A:AIN1_49") (pintype "bidirectional"))
    )
    (net (code "48") (name "Net-(D6A-AC)") (class "Default")
      (node (ref "D6") (pin "4") (pinfunction "AC_4") (pintype "passive"))
      (node (ref "R14") (pin "8") (pinfunction "2_8") (pintype "passive"))
      (node (ref "U3") (pin "53") (pinfunction "PE7:ICP3:INT7:CLK0_53") (pintype "bidirectional"))
    )
    (net (code "49") (name "Net-(D6B-AC)") (class "Default")
      (node (ref "D6") (pin "1") (pinfunction "AC_1") (pintype "passive"))
      (node (ref "R14") (pin "6") (pinfunction "2_6") (pintype "passive"))
      (node (ref "U3") (pin "50") (pinfunction "PE4:OC3B:INT4_50") (pintype "bidirectional"))
    )
    (net (code "50") (name "Net-(D7A-AC)") (class "Default")
      (node (ref "D7") (pin "4") (pinfunction "AC_4") (pintype "passive"))
      (node (ref "R12") (pin "2") (pinfunction "2_2") (pintype "passive"))
      (node (ref "U3") (pin "63") (pinfunction "PF0:ADC0_63") (pintype "bidirectional"))
    )
    (net (code "51") (name "Net-(D7B-AC)") (class "Default")
      (node (ref "D7") (pin "1") (pinfunction "AC_1") (pintype "passive"))
      (node (ref "R12") (pin "4") (pinfunction "2_4") (pintype "passive"))
      (node (ref "U3") (pin "64") (pinfunction "PF1:ADC1_64") (pintype "bidirectional"))
    )
    (net (code "52") (name "Net-(D8A-AC)") (class "Default")
      (node (ref "D8") (pin "4") (pinfunction "AC_4") (pintype "passive"))
      (node (ref "R12") (pin "8") (pinfunction "2_8") (pintype "passive"))
      (node (ref "U3") (pin "2") (pinfunction "PF3:ADC3:DIG4_2") (pintype "bidirectional"))
    )
    (net (code "53") (name "Net-(D8B-AC)") (class "Default")
      (node (ref "D8") (pin "1") (pinfunction "AC_1") (pintype "passive"))
      (node (ref "R12") (pin "6") (pinfunction "2_6") (pintype "passive"))
      (node (ref "U3") (pin "1") (pinfunction "PF2:ADC2:DIG2_1") (pintype "bidirectional"))
    )
    (net (code "54") (name "Net-(D9A-AC)") (class "Default")
      (node (ref "D9") (pin "4") (pinfunction "AC_4") (pintype "passive"))
      (node (ref "R17") (pin "4") (pinfunction "2_4") (pintype "passive"))
      (node (ref "U3") (pin "4") (pinfunction "PF5:ADC5:TMS_4") (pintype "bidirectional"))
    )
    (net (code "55") (name "Net-(D9B-AC)") (class "Default")
      (node (ref "D9") (pin "1") (pinfunction "AC_1") (pintype "passive"))
      (node (ref "R17") (pin "2") (pinfunction "2_2") (pintype "passive"))
      (node (ref "U3") (pin "3") (pinfunction "PF4:ADC4:TCK_3") (pintype "bidirectional"))
    )
    (net (code "56") (name "Net-(D10A-AC)") (class "Default")
      (node (ref "D10") (pin "4") (pinfunction "AC_4") (pintype "passive"))
      (node (ref "R13") (pin "6") (pinfunction "2_6") (pintype "passive"))
      (node (ref "U3") (pin "43") (pinfunction "PB7:OC0A:OC1C:PCINT7_43") (pintype "bidirectional"))
    )
    (net (code "57") (name "Net-(D10B-AC)") (class "Default")
      (node (ref "D10") (pin "1") (pinfunction "AC_1") (pintype "passive"))
      (node (ref "R13") (pin "8") (pinfunction "2_8") (pintype "passive"))
      (node (ref "U3") (pin "42") (pinfunction "PB6:OC1B:PCINT6_42") (pintype "bidirectional"))
    )
    (net (code "58") (name "Net-(D11-J-Pad2)") (class "Default")
      (node (ref "D11-J") (pin "2") (pinfunction "2_2") (pintype "passive"))
      (node (ref "DIGITAL1") (pin "4") (pinfunction "4_4") (pintype "passive"))
    )
    (net (code "59") (name "Net-(D11B-AC)") (class "Default")
      (node (ref "D11") (pin "1") (pinfunction "AC_1") (pintype "passive"))
      (node (ref "R13") (pin "4") (pinfunction "2_4") (pintype "passive"))
      (node (ref "U3") (pin "40") (pinfunction "PB4:OC2A:PCINT4_40") (pintype "bidirectional"))
    )
    (net (code "60") (name "Net-(D12A-AC)") (class "Default")
      (node (ref "D12") (pin "4") (pinfunction "AC_4") (pintype "passive"))
      (node (ref "R16") (pin "4") (pinfunction "2_4") (pintype "passive"))
      (node (ref "U3") (pin "41") (pinfunction "PB5:OC1A:PCINT5_41") (pintype "bidirectional"))
    )
    (net (code "61") (name "Net-(DIGITAL0-Pad1)") (class "Default")
      (node (ref "DIGITAL0") (pin "1") (pinfunction "1_1") (pintype "passive"))
      (node (ref "R15") (pin "1") (pinfunction "1_1") (pintype "passive"))
    )
    (net (code "62") (name "Net-(DIGITAL0-Pad5)") (class "Default")
      (node (ref "DIGITAL0") (pin "5") (pinfunction "5_5") (pintype "passive"))
      (node (ref "R14") (pin "1") (pinfunction "1_1") (pintype "passive"))
    )
    (net (code "63") (name "Net-(DIGITAL1-Pad5)") (class "Default")
      (node (ref "DIGITAL1") (pin "5") (pinfunction "5_5") (pintype "passive"))
      (node (ref "R16") (pin "1") (pinfunction "1_1") (pintype "passive"))
      (node (ref "SPI") (pin "2") (pinfunction "2_2") (pintype "passive"))
    )
    (net (code "64") (name "Net-(L-PadA)") (class "Default")
      (node (ref "L") (pin "A") (pinfunction "A_A") (pintype "passive"))
      (node (ref "R7") (pin "2") (pinfunction "2_2") (pintype "passive"))
    )
    (net (code "65") (name "Net-(PWR-PadA)") (class "Default")
      (node (ref "PWR") (pin "A") (pinfunction "A_A") (pintype "passive"))
      (node (ref "R6") (pin "2") (pinfunction "2_2") (pintype "passive"))
    )
    (net (code "66") (name "Net-(R7B-2)") (class "Default")
      (node (ref "R7") (pin "4") (pinfunction "2_4") (pintype "passive"))
      (node (ref "TX") (pin "A") (pinfunction "A_A") (pintype "passive"))
    )
    (net (code "67") (name "Net-(R7D-2)") (class "Default")
      (node (ref "R7") (pin "8") (pinfunction "2_8") (pintype "passive"))
      (node (ref "RX") (pin "A") (pinfunction "A_A") (pintype "passive"))
    )
    (net (code "68") (name "Net-(R8-Pad2)") (class "Default")
      (node (ref "R8") (pin "2") (pinfunction "2_2") (pintype "passive"))
      (node (ref "RFRX") (pin "C") (pinfunction "C_C") (pintype "passive"))
    )
    (net (code "69") (name "Net-(R9-Pad2)") (class "Default")
      (node (ref "R9") (pin "2") (pinfunction "2_2") (pintype "passive"))
      (node (ref "RFTX") (pin "C") (pinfunction "C_C") (pintype "passive"))
    )
    (net (code "70") (name "Net-(R12B-1)") (class "Default")
      (node (ref "ANALOG") (pin "2") (pinfunction "2_2") (pintype "passive"))
      (node (ref "R12") (pin "3") (pinfunction "1_3") (pintype "passive"))
    )
    (net (code "71") (name "Net-(R12C-1)") (class "Default")
      (node (ref "ANALOG") (pin "3") (pinfunction "3_3") (pintype "passive"))
      (node (ref "R12") (pin "5") (pinfunction "1_5") (pintype "passive"))
    )
    (net (code "72") (name "Net-(R12D-1)") (class "Default")
      (node (ref "ANALOG") (pin "4") (pinfunction "4_4") (pintype "passive"))
      (node (ref "R12") (pin "7") (pinfunction "1_7") (pintype "passive"))
    )
    (net (code "73") (name "Net-(R13B-1)") (class "Default")
      (node (ref "DIGITAL1") (pin "1") (pinfunction "1_1") (pintype "passive"))
      (node (ref "R13") (pin "3") (pinfunction "1_3") (pintype "passive"))
    )
    (net (code "74") (name "Net-(R13C-1)") (class "Default")
      (node (ref "DIGITAL1") (pin "2") (pinfunction "2_2") (pintype "passive"))
      (node (ref "R13") (pin "5") (pinfunction "1_5") (pintype "passive"))
    )
    (net (code "75") (name "Net-(R13D-1)") (class "Default")
      (node (ref "DIGITAL1") (pin "3") (pinfunction "3_3") (pintype "passive"))
      (node (ref "R13") (pin "7") (pinfunction "1_7") (pintype "passive"))
    )
    (net (code "76") (name "Net-(R14B-1)") (class "Default")
      (node (ref "DIGITAL0") (pin "6") (pinfunction "6_6") (pintype "passive"))
      (node (ref "R14") (pin "3") (pinfunction "1_3") (pintype "passive"))
    )
    (net (code "77") (name "Net-(R14C-1)") (class "Default")
      (node (ref "DIGITAL0") (pin "7") (pinfunction "7_7") (pintype "passive"))
      (node (ref "R14") (pin "5") (pinfunction "1_5") (pintype "passive"))
    )
    (net (code "78") (name "Net-(R14D-1)") (class "Default")
      (node (ref "DIGITAL0") (pin "8") (pinfunction "8_8") (pintype "passive"))
      (node (ref "R14") (pin "7") (pinfunction "1_7") (pintype "passive"))
    )
    (net (code "79") (name "Net-(R15B-1)") (class "Default")
      (node (ref "DIGITAL0") (pin "2") (pinfunction "2_2") (pintype "passive"))
      (node (ref "R15") (pin "3") (pinfunction "1_3") (pintype "passive"))
    )
    (net (code "80") (name "Net-(R15C-1)") (class "Default")
      (node (ref "DIGITAL0") (pin "3") (pinfunction "3_3") (pintype "passive"))
      (node (ref "R15") (pin "5") (pinfunction "1_5") (pintype "passive"))
    )
    (net (code "81") (name "Net-(R15D-1)") (class "Default")
      (node (ref "DIGITAL0") (pin "4") (pinfunction "4_4") (pintype "passive"))
      (node (ref "R15") (pin "7") (pinfunction "1_7") (pintype "passive"))
    )
    (net (code "82") (name "Net-(R16C-1)") (class "Default")
      (node (ref "DIGITAL1") (pin "6") (pinfunction "6_6") (pintype "passive"))
      (node (ref "R16") (pin "5") (pinfunction "1_5") (pintype "passive"))
      (node (ref "SPI") (pin "1") (pinfunction "1_1") (pintype "passive"))
    )
    (net (code "83") (name "Net-(R16D-1)") (class "Default")
      (node (ref "D11-J") (pin "1") (pinfunction "1_1") (pintype "passive"))
      (node (ref "R16") (pin "7") (pinfunction "1_7") (pintype "passive"))
      (node (ref "SPI") (pin "3") (pinfunction "3_3") (pintype "passive"))
    )
    (net (code "84") (name "Net-(R17B-1)") (class "Default")
      (node (ref "A6-J") (pin "1") (pinfunction "1_1") (pintype "passive"))
      (node (ref "R17") (pin "3") (pinfunction "1_3") (pintype "passive"))
    )
    (net (code "85") (name "Net-(U3-AVDD)") (class "Default")
      (node (ref "C18") (pin "2") (pinfunction "2_2") (pintype "passive"))
      (node (ref "U3") (pin "60") (pinfunction "AVDD_60") (pintype "bidirectional"))
    )
    (net (code "86") (name "Net-(U3-PF6:ADC6:TDO)") (class "Default")
      (node (ref "AUX") (pin "13") (pinfunction "13_13") (pintype "passive"))
      (node (ref "U3") (pin "5") (pinfunction "PF6:ADC6:TDO_5") (pintype "bidirectional"))
    )
    (net (code "87") (name "Net-(U3-PF7:ADC7:TDI)") (class "Default")
      (node (ref "AUX") (pin "11") (pinfunction "11_11") (pintype "passive"))
      (node (ref "U3") (pin "6") (pinfunction "PF7:ADC7:TDI_6") (pintype "bidirectional"))
    )
    (net (code "88") (name "Net-(U3-PG0:DIG3)") (class "Default")
      (node (ref "AUX") (pin "12") (pinfunction "12_12") (pintype "passive"))
      (node (ref "U3") (pin "14") (pinfunction "PG0:DIG3_14") (pintype "bidirectional"))
    )
    (net (code "89") (name "Net-(U3-PG1:DIG1)") (class "Default")
      (node (ref "AUX") (pin "9") (pinfunction "9_9") (pintype "passive"))
      (node (ref "U3") (pin "15") (pinfunction "PG1:DIG1_15") (pintype "bidirectional"))
    )
    (net (code "90") (name "Net-(U3-PG2:AMR)") (class "Default")
      (node (ref "AUX") (pin "10") (pinfunction "10_10") (pintype "passive"))
      (node (ref "U3") (pin "16") (pinfunction "PG2:AMR_16") (pintype "bidirectional"))
    )
    (net (code "91") (name "Net-(U3-PG3:TOSC2)") (class "Default")
      (node (ref "AUX") (pin "7") (pinfunction "7_7") (pintype "passive"))
      (node (ref "C8") (pin "2") (pinfunction "2_2") (pintype "passive"))
      (node (ref "Q2") (pin "1") (pinfunction "1_1") (pintype "passive"))
      (node (ref "U3") (pin "17") (pinfunction "PG3:TOSC2_17") (pintype "bidirectional"))
    )
    (net (code "92") (name "Net-(U3-PG4:TOSC1)") (class "Default")
      (node (ref "AUX") (pin "8") (pinfunction "8_8") (pintype "passive"))
      (node (ref "C7") (pin "2") (pinfunction "2_2") (pintype "passive"))
      (node (ref "Q2") (pin "2") (pinfunction "2_2") (pintype "passive"))
      (node (ref "U3") (pin "18") (pinfunction "PG4:TOSC1_18") (pintype "bidirectional"))
    )
    (net (code "93") (name "Net-(U3-PG5:OC0B)") (class "Default")
      (node (ref "AUX") (pin "5") (pinfunction "5_5") (pintype "passive"))
      (node (ref "U3") (pin "19") (pinfunction "PG5:OC0B_19") (pintype "bidirectional"))
    )
    (net (code "94") (name "Net-(U3-RFN)") (class "Default")
      (node (ref "C13") (pin "2") (pinfunction "2_2") (pintype "passive"))
      (node (ref "U3") (pin "9") (pinfunction "RFN_9") (pintype "bidirectional"))
    )
    (net (code "95") (name "Net-(U3-RFP)") (class "Default")
      (node (ref "C12") (pin "2") (pinfunction "2_2") (pintype "passive"))
      (node (ref "U3") (pin "8") (pinfunction "RFP_8") (pintype "bidirectional"))
    )
    (net (code "96") (name "Net-(U3-XTAL1)") (class "Default")
      (node (ref "C2") (pin "2") (pinfunction "2_2") (pintype "passive"))
      (node (ref "Q1") (pin "2") (pinfunction "2_2") (pintype "passive"))
      (node (ref "U3") (pin "56") (pinfunction "XTAL1_56") (pintype "bidirectional"))
    )
    (net (code "97") (name "Net-(U3-XTAL2)") (class "Default")
      (node (ref "C1") (pin "2") (pinfunction "2_2") (pintype "passive"))
      (node (ref "Q1") (pin "1") (pinfunction "1_1") (pintype "passive"))
      (node (ref "U3") (pin "57") (pinfunction "XTAL2_57") (pintype "bidirectional"))
    )
    (net (code "98") (name "Net-(U4-3V3OUT)") (class "Default")
      (node (ref "C21") (pin "1") (pinfunction "1_1") (pintype "passive"))
      (node (ref "U4") (pin "13") (pinfunction "3V3OUT_13") (pintype "bidirectional"))
      (node (ref "U4") (pin "14") (pinfunction "RESET#_14") (pintype "bidirectional"))
      (node (ref "U4") (pin "3") (pinfunction "VCCIO_3") (pintype "bidirectional"))
    )
    (net (code "99") (name "Net-(U4-DTR#)") (class "Default")
      (node (ref "C11") (pin "1") (pinfunction "1_1") (pintype "passive"))
      (node (ref "U4") (pin "1") (pinfunction "DTR#_1") (pintype "bidirectional"))
    )
    (net (code "100") (name "Net-(U4-USBDM)") (class "Default")
      (node (ref "R4") (pin "2") (pinfunction "2_2") (pintype "passive"))
      (node (ref "U4") (pin "12") (pinfunction "USBDM_12") (pintype "bidirectional"))
    )
    (net (code "101") (name "Net-(U4-USBDP)") (class "Default")
      (node (ref "R5") (pin "2") (pinfunction "2_2") (pintype "passive"))
      (node (ref "U4") (pin "11") (pinfunction "USBDP_11") (pintype "bidirectional"))
    )
    (net (code "102") (name "Net-(U4-VCC)") (class "Default")
      (node (ref "L1") (pin "2") (pinfunction "2_2") (pintype "passive"))
      (node (ref "U4") (pin "15") (pinfunction "VCC_15") (pintype "bidirectional"))
    )
    (net (code "103") (name "Net-(U5A-OUT)") (class "Default")
      (node (ref "U5") (pin "1") (pinfunction "OUT_1") (pintype "output"))
      (node (ref "U5") (pin "5") (pinfunction "+IN_5") (pintype "input"))
    )
    (net (code "104") (name "Net-(U7-PROG)") (class "Default")
      (node (ref "R2") (pin "2") (pinfunction "2_2") (pintype "passive"))
      (node (ref "U7") (pin "5") (pinfunction "PROG_5") (pintype "input"))
    )
    (net (code "105") (name "Net-(U7-STAT)") (class "Default")
      (node (ref "R3") (pin "1") (pinfunction "1_1") (pintype "passive"))
      (node (ref "U7") (pin "1") (pinfunction "STAT_1") (pintype "output"))
    )
    (net (code "106") (name "Net-(U7-VBAT)") (class "Default")
      (node (ref "C3") (pin "1") (pinfunction "1_1") (pintype "passive"))
      (node (ref "D14") (pin "A") (pinfunction "A_A") (pintype "passive"))
      (node (ref "JP1") (pin "2") (pinfunction "2_2") (pintype "passive"))
      (node (ref "U7") (pin "3") (pinfunction "VBAT_3") (pintype "power_in"))
    )
    (net (code "107") (name "unconnected-(POWER-Pad1)") (class "Default")
      (node (ref "POWER") (pin "1") (pinfunction "1_1") (pintype "passive"))
    )
    (net (code "108") (name "unconnected-(U3-~{RESET_OUT}-Pad13)") (class "Default")
      (node (ref "U3") (pin "13") (pinfunction "~{RESET_OUT}_13") (pintype "bidirectional"))
    )
    (net (code "109") (name "unconnected-(U4-CBUS0-Pad18)") (class "Default")
      (node (ref "U4") (pin "18") (pinfunction "CBUS0_18") (pintype "bidirectional"))
    )
    (net (code "110") (name "unconnected-(U4-CBUS3-Pad19)") (class "Default")
      (node (ref "U4") (pin "19") (pinfunction "CBUS3_19") (pintype "bidirectional"))
    )
    (net (code "111") (name "unconnected-(U4-CTS#-Pad9)") (class "Default")
      (node (ref "U4") (pin "9") (pinfunction "CTS#_9") (pintype "bidirectional"))
    )
    (net (code "112") (name "unconnected-(U4-DCD#-Pad8)") (class "Default")
      (node (ref "U4") (pin "8") (pinfunction "DCD#_8") (pintype "bidirectional"))
    )
    (net (code "113") (name "unconnected-(U4-DSR#-Pad7)") (class "Default")
      (node (ref "U4") (pin "7") (pinfunction "DSR#_7") (pintype "bidirectional"))
    )
    (net (code "114") (name "unconnected-(U4-RI#-Pad5)") (class "Default")
      (node (ref "U4") (pin "5") (pinfunction "RI#_5") (pintype "bidirectional"))
    )
    (net (code "115") (name "unconnected-(U4-RTS#-Pad2)") (class "Default")
      (node (ref "U4") (pin "2") (pinfunction "RTS#_2") (pintype "bidirectional"))
    )
  )
)
